# tweety.net
KiCad netlist of a schematic drawn in EAGLE
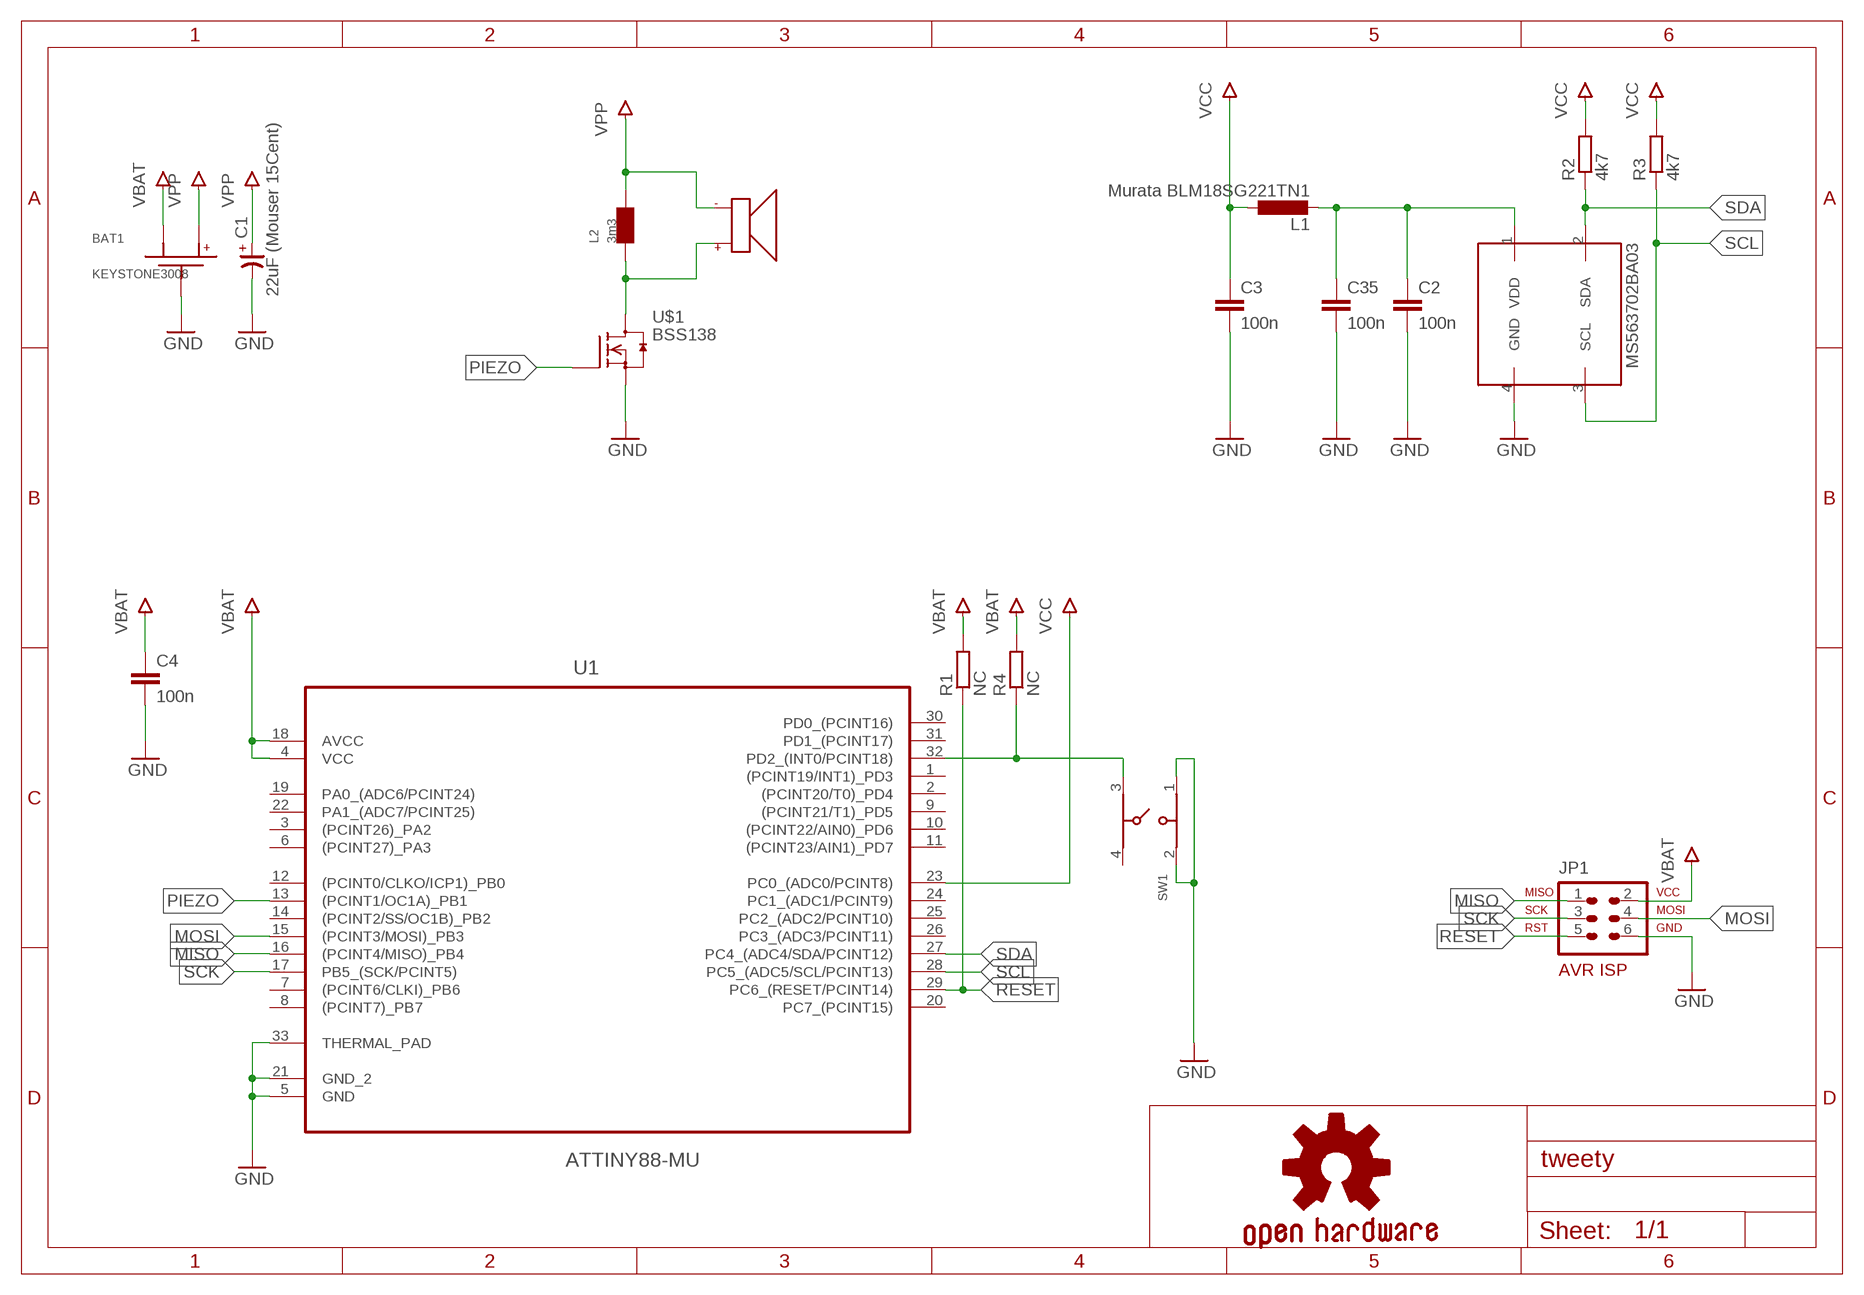
[diagram p0: schematic, sheet 1]

(export (version "E")
  (design (tool "Eeschema 10.0.6"))
  (components
    (comp (ref "BAT1")
      (value "KEYSTONE3008")
      (footprint "eagle-import:KEYSTONE3008")
      (libsource (lib "eagle-import") (part "KEYSTONE3008"))
    )
    (comp (ref "C1")
      (value "22uF (Mouser 15Cent)")
      (footprint "eagle-import:3528-21R_T")
      (libsource (lib "eagle-import") (part "CP-3528-21R"))
    )
    (comp (ref "C2")
      (value "100n")
      (footprint "eagle-import:C0603")
      (libsource (lib "eagle-import") (part "C-EUC0603"))
    )
    (comp (ref "C3")
      (value "100n")
      (footprint "eagle-import:C0603")
      (libsource (lib "eagle-import") (part "C-EUC0603"))
    )
    (comp (ref "C4")
      (value "100n")
      (footprint "eagle-import:C0603")
      (libsource (lib "eagle-import") (part "C-EUC0603"))
    )
    (comp (ref "C35")
      (value "100n")
      (footprint "eagle-import:C0603")
      (libsource (lib "eagle-import") (part "C-EUC0603"))
    )
    (comp (ref "GOLD_ORB_SM1")
      (value "OSHWLOGO_GOLD_ORB_MED")
      (footprint "eagle-import:OSHW1")
      (libsource (lib "eagle-import") (part "OSHWLOGO_GOLD_ORB_MED"))
    )
    (comp (ref "IC2")
      (value "MS563702BA03")
      (footprint "eagle-import:MS5637")
      (libsource (lib "eagle-import") (part "MS563702BA03"))
    )
    (comp (ref "JP1")
      (value "AVR-ISP-6VERT")
      (footprint "eagle-import:AVR-ISP-6")
      (libsource (lib "eagle-import") (part "AVR-ISP-6VERT"))
    )
    (comp (ref "L1")
      (value "Murata BLM18SG221TN1")
      (footprint "eagle-import:L0603")
      (libsource (lib "eagle-import") (part "L-EUL0603"))
    )
    (comp (ref "L2")
      (value "3m3")
      (footprint "eagle-import:SDR0503")
      (libsource (lib "eagle-import") (part "SDR0503"))
    )
    (comp (ref "P2")
      (value "PKLCS1212E2400")
      (footprint "eagle-import:PKLCS1212")
      (libsource (lib "eagle-import") (part "PKLCS1212E2400"))
    )
    (comp (ref "R1")
      (value "NC")
      (footprint "eagle-import:R0603")
      (libsource (lib "eagle-import") (part "R-EU_R0603"))
    )
    (comp (ref "R2")
      (value "4k7")
      (footprint "eagle-import:R0603")
      (libsource (lib "eagle-import") (part "R-EU_R0603"))
    )
    (comp (ref "R3")
      (value "4k7")
      (footprint "eagle-import:R0603")
      (libsource (lib "eagle-import") (part "R-EU_R0603"))
    )
    (comp (ref "R4")
      (value "NC")
      (footprint "eagle-import:R0603")
      (libsource (lib "eagle-import") (part "R-EU_R0603"))
    )
    (comp (ref "SW1")
      (value "4301X20858X6")
      (footprint "eagle-import:4301X20858X6")
      (libsource (lib "eagle-import") (part "4301X20858X6"))
    )
    (comp (ref "U$1")
      (value "BSS138")
      (footprint "eagle-import:SOT23")
      (libsource (lib "eagle-import") (part "BSS138"))
    )
    (comp (ref "U1")
      (value "ATTINY88-MU")
      (footprint "eagle-import:QFN50P500X500X100-33N")
      (libsource (lib "eagle-import") (part "ATTINY88-MU"))
    )
  )
  (nets
    (net (code "1") (name "GND") (class "Default")
      (node (ref "BAT1") (pin "N") (pinfunction "N_N") (pintype "bidirectional"))
      (node (ref "C1") (pin "-") (pinfunction "-_-") (pintype "passive"))
      (node (ref "C2") (pin "2") (pinfunction "2_2") (pintype "passive"))
      (node (ref "C3") (pin "2") (pinfunction "2_2") (pintype "passive"))
      (node (ref "C35") (pin "2") (pinfunction "2_2") (pintype "passive"))
      (node (ref "C4") (pin "2") (pinfunction "2_2") (pintype "passive"))
      (node (ref "IC2") (pin "4") (pinfunction "GND_4") (pintype "bidirectional"))
      (node (ref "JP1") (pin "6") (pinfunction "6_6") (pintype "passive"))
      (node (ref "SW1") (pin "1") (pinfunction "1_1") (pintype "passive"))
      (node (ref "SW1") (pin "2") (pinfunction "2_2") (pintype "passive"))
      (node (ref "U$1") (pin "2") (pinfunction "S_2") (pintype "passive"))
      (node (ref "U1") (pin "21") (pinfunction "GND_2_21") (pintype "passive"))
      (node (ref "U1") (pin "33") (pinfunction "THERMAL_PAD_33") (pintype "passive"))
      (node (ref "U1") (pin "5") (pinfunction "GND_5") (pintype "passive"))
    )
    (net (code "2") (name "MISO") (class "Default")
      (node (ref "JP1") (pin "1") (pinfunction "1_1") (pintype "passive"))
      (node (ref "U1") (pin "16") (pinfunction "(PCINT4/MISO)_PB4_16") (pintype "bidirectional"))
    )
    (net (code "3") (name "MOSI") (class "Default")
      (node (ref "JP1") (pin "4") (pinfunction "4_4") (pintype "passive"))
      (node (ref "U1") (pin "15") (pinfunction "(PCINT3/MOSI)_PB3_15") (pintype "bidirectional"))
    )
    (net (code "4") (name "Net-(IC2-VDD)") (class "Default")
      (node (ref "C2") (pin "1") (pinfunction "1_1") (pintype "passive"))
      (node (ref "C35") (pin "1") (pinfunction "1_1") (pintype "passive"))
      (node (ref "IC2") (pin "1") (pinfunction "VDD_1") (pintype "bidirectional"))
      (node (ref "L1") (pin "2") (pinfunction "2_2") (pintype "passive"))
    )
    (net (code "5") (name "Net-(U$1-D)") (class "Default")
      (node (ref "L2") (pin "P$1") (pinfunction "P$1_P$1") (pintype "bidirectional"))
      (node (ref "P2") (pin "P$+") (pinfunction "P$+_P$+") (pintype "bidirectional"))
      (node (ref "U$1") (pin "3") (pinfunction "D_3") (pintype "passive"))
    )
    (net (code "6") (name "Net-(U1-PD2_(INT0{slash}PCINT18))") (class "Default")
      (node (ref "R4") (pin "1") (pinfunction "1_1") (pintype "passive"))
      (node (ref "SW1") (pin "3") (pinfunction "3_3") (pintype "passive"))
      (node (ref "U1") (pin "32") (pinfunction "PD2_(INT0/PCINT18)_32") (pintype "bidirectional"))
    )
    (net (code "7") (name "PIEZO") (class "Default")
      (node (ref "U$1") (pin "1") (pinfunction "G_1") (pintype "passive"))
      (node (ref "U1") (pin "13") (pinfunction "(PCINT1/OC1A)_PB1_13") (pintype "bidirectional"))
    )
    (net (code "8") (name "RESET") (class "Default")
      (node (ref "JP1") (pin "5") (pinfunction "5_5") (pintype "passive"))
      (node (ref "R1") (pin "1") (pinfunction "1_1") (pintype "passive"))
      (node (ref "U1") (pin "29") (pinfunction "PC6_(RESET/PCINT14)_29") (pintype "bidirectional"))
    )
    (net (code "9") (name "SCK") (class "Default")
      (node (ref "JP1") (pin "3") (pinfunction "3_3") (pintype "passive"))
      (node (ref "U1") (pin "17") (pinfunction "PB5_(SCK/PCINT5)_17") (pintype "bidirectional"))
    )
    (net (code "10") (name "SCL") (class "Default")
      (node (ref "IC2") (pin "3") (pinfunction "SCL_3") (pintype "bidirectional"))
      (node (ref "R3") (pin "1") (pinfunction "1_1") (pintype "passive"))
      (node (ref "U1") (pin "28") (pinfunction "PC5_(ADC5/SCL/PCINT13)_28") (pintype "bidirectional"))
    )
    (net (code "11") (name "SDA") (class "Default")
      (node (ref "IC2") (pin "2") (pinfunction "SDA_2") (pintype "bidirectional"))
      (node (ref "R2") (pin "1") (pinfunction "1_1") (pintype "passive"))
      (node (ref "U1") (pin "27") (pinfunction "PC4_(ADC4/SDA/PCINT12)_27") (pintype "bidirectional"))
    )
    (net (code "12") (name "VBAT") (class "Default")
      (node (ref "BAT1") (pin "P$3") (pinfunction "P1_P$3") (pintype "bidirectional"))
      (node (ref "C4") (pin "1") (pinfunction "1_1") (pintype "passive"))
      (node (ref "JP1") (pin "2") (pinfunction "2_2") (pintype "passive"))
      (node (ref "R1") (pin "2") (pinfunction "2_2") (pintype "passive"))
      (node (ref "R4") (pin "2") (pinfunction "2_2") (pintype "passive"))
      (node (ref "U1") (pin "18") (pinfunction "AVCC_18") (pintype "power_in"))
      (node (ref "U1") (pin "4") (pinfunction "VCC_4") (pintype "power_in"))
    )
    (net (code "13") (name "VCC") (class "Default")
      (node (ref "C3") (pin "1") (pinfunction "1_1") (pintype "passive"))
      (node (ref "L1") (pin "1") (pinfunction "1_1") (pintype "passive"))
      (node (ref "R2") (pin "2") (pinfunction "2_2") (pintype "passive"))
      (node (ref "R3") (pin "2") (pinfunction "2_2") (pintype "passive"))
      (node (ref "U1") (pin "23") (pinfunction "PC0_(ADC0/PCINT8)_23") (pintype "bidirectional"))
    )
    (net (code "14") (name "VPP") (class "Default")
      (node (ref "BAT1") (pin "P$4") (pinfunction "P2_P$4") (pintype "bidirectional"))
      (node (ref "C1") (pin "+") (pinfunction "+_+") (pintype "passive"))
      (node (ref "L2") (pin "P$2") (pinfunction "P$2_P$2") (pintype "bidirectional"))
      (node (ref "P2") (pin "P$-") (pinfunction "P$-_P$-") (pintype "bidirectional"))
    )
    (net (code "15") (name "unconnected-(SW1-Pad4)") (class "Default")
      (node (ref "SW1") (pin "4") (pinfunction "4_4") (pintype "passive"))
    )
    (net (code "16") (name "unconnected-(U1-(PCINT0{slash}CLKO{slash}ICP1)_PB0-Pad12)") (class "Default")
      (node (ref "U1") (pin "12") (pinfunction "(PCINT0/CLKO/ICP1)_PB0_12") (pintype "bidirectional"))
    )
    (net (code "17") (name "unconnected-(U1-(PCINT2{slash}SS{slash}OC1B)_PB2-Pad14)") (class "Default")
      (node (ref "U1") (pin "14") (pinfunction "(PCINT2/SS/OC1B)_PB2_14") (pintype "bidirectional"))
    )
    (net (code "18") (name "unconnected-(U1-(PCINT6{slash}CLKI)_PB6-Pad7)") (class "Default")
      (node (ref "U1") (pin "7") (pinfunction "(PCINT6/CLKI)_PB6_7") (pintype "bidirectional"))
    )
    (net (code "19") (name "unconnected-(U1-(PCINT7)_PB7-Pad8)") (class "Default")
      (node (ref "U1") (pin "8") (pinfunction "(PCINT7)_PB7_8") (pintype "bidirectional"))
    )
    (net (code "20") (name "unconnected-(U1-(PCINT19{slash}INT1)_PD3-Pad1)") (class "Default")
      (node (ref "U1") (pin "1") (pinfunction "(PCINT19/INT1)_PD3_1") (pintype "bidirectional"))
    )
    (net (code "21") (name "unconnected-(U1-(PCINT20{slash}T0)_PD4-Pad2)") (class "Default")
      (node (ref "U1") (pin "2") (pinfunction "(PCINT20/T0)_PD4_2") (pintype "bidirectional"))
    )
    (net (code "22") (name "unconnected-(U1-(PCINT21{slash}T1)_PD5-Pad9)") (class "Default")
      (node (ref "U1") (pin "9") (pinfunction "(PCINT21/T1)_PD5_9") (pintype "bidirectional"))
    )
    (net (code "23") (name "unconnected-(U1-(PCINT22{slash}AIN0)_PD6-Pad10)") (class "Default")
      (node (ref "U1") (pin "10") (pinfunction "(PCINT22/AIN0)_PD6_10") (pintype "bidirectional"))
    )
    (net (code "24") (name "unconnected-(U1-(PCINT23{slash}AIN1)_PD7-Pad11)") (class "Default")
      (node (ref "U1") (pin "11") (pinfunction "(PCINT23/AIN1)_PD7_11") (pintype "bidirectional"))
    )
    (net (code "25") (name "unconnected-(U1-(PCINT26)_PA2-Pad3)") (class "Default")
      (node (ref "U1") (pin "3") (pinfunction "(PCINT26)_PA2_3") (pintype "bidirectional"))
    )
    (net (code "26") (name "unconnected-(U1-(PCINT27)_PA3-Pad6)") (class "Default")
      (node (ref "U1") (pin "6") (pinfunction "(PCINT27)_PA3_6") (pintype "bidirectional"))
    )
    (net (code "27") (name "unconnected-(U1-PA0_(ADC6{slash}PCINT24)-Pad19)") (class "Default")
      (node (ref "U1") (pin "19") (pinfunction "PA0_(ADC6/PCINT24)_19") (pintype "bidirectional"))
    )
    (net (code "28") (name "unconnected-(U1-PA1_(ADC7{slash}PCINT25)-Pad22)") (class "Default")
      (node (ref "U1") (pin "22") (pinfunction "PA1_(ADC7/PCINT25)_22") (pintype "bidirectional"))
    )
    (net (code "29") (name "unconnected-(U1-PC1_(ADC1{slash}PCINT9)-Pad24)") (class "Default")
      (node (ref "U1") (pin "24") (pinfunction "PC1_(ADC1/PCINT9)_24") (pintype "bidirectional"))
    )
    (net (code "30") (name "unconnected-(U1-PC2_(ADC2{slash}PCINT10)-Pad25)") (class "Default")
      (node (ref "U1") (pin "25") (pinfunction "PC2_(ADC2/PCINT10)_25") (pintype "bidirectional"))
    )
    (net (code "31") (name "unconnected-(U1-PC3_(ADC3{slash}PCINT11)-Pad26)") (class "Default")
      (node (ref "U1") (pin "26") (pinfunction "PC3_(ADC3/PCINT11)_26") (pintype "bidirectional"))
    )
    (net (code "32") (name "unconnected-(U1-PC7_(PCINT15)-Pad20)") (class "Default")
      (node (ref "U1") (pin "20") (pinfunction "PC7_(PCINT15)_20") (pintype "bidirectional"))
    )
    (net (code "33") (name "unconnected-(U1-PD0_(PCINT16)-Pad30)") (class "Default")
      (node (ref "U1") (pin "30") (pinfunction "PD0_(PCINT16)_30") (pintype "bidirectional"))
    )
    (net (code "34") (name "unconnected-(U1-PD1_(PCINT17)-Pad31)") (class "Default")
      (node (ref "U1") (pin "31") (pinfunction "PD1_(PCINT17)_31") (pintype "bidirectional"))
    )
  )
)
